# Gagabiro_POC_PSU_main.net
KiCad netlist of a schematic drawn in Altium Designer
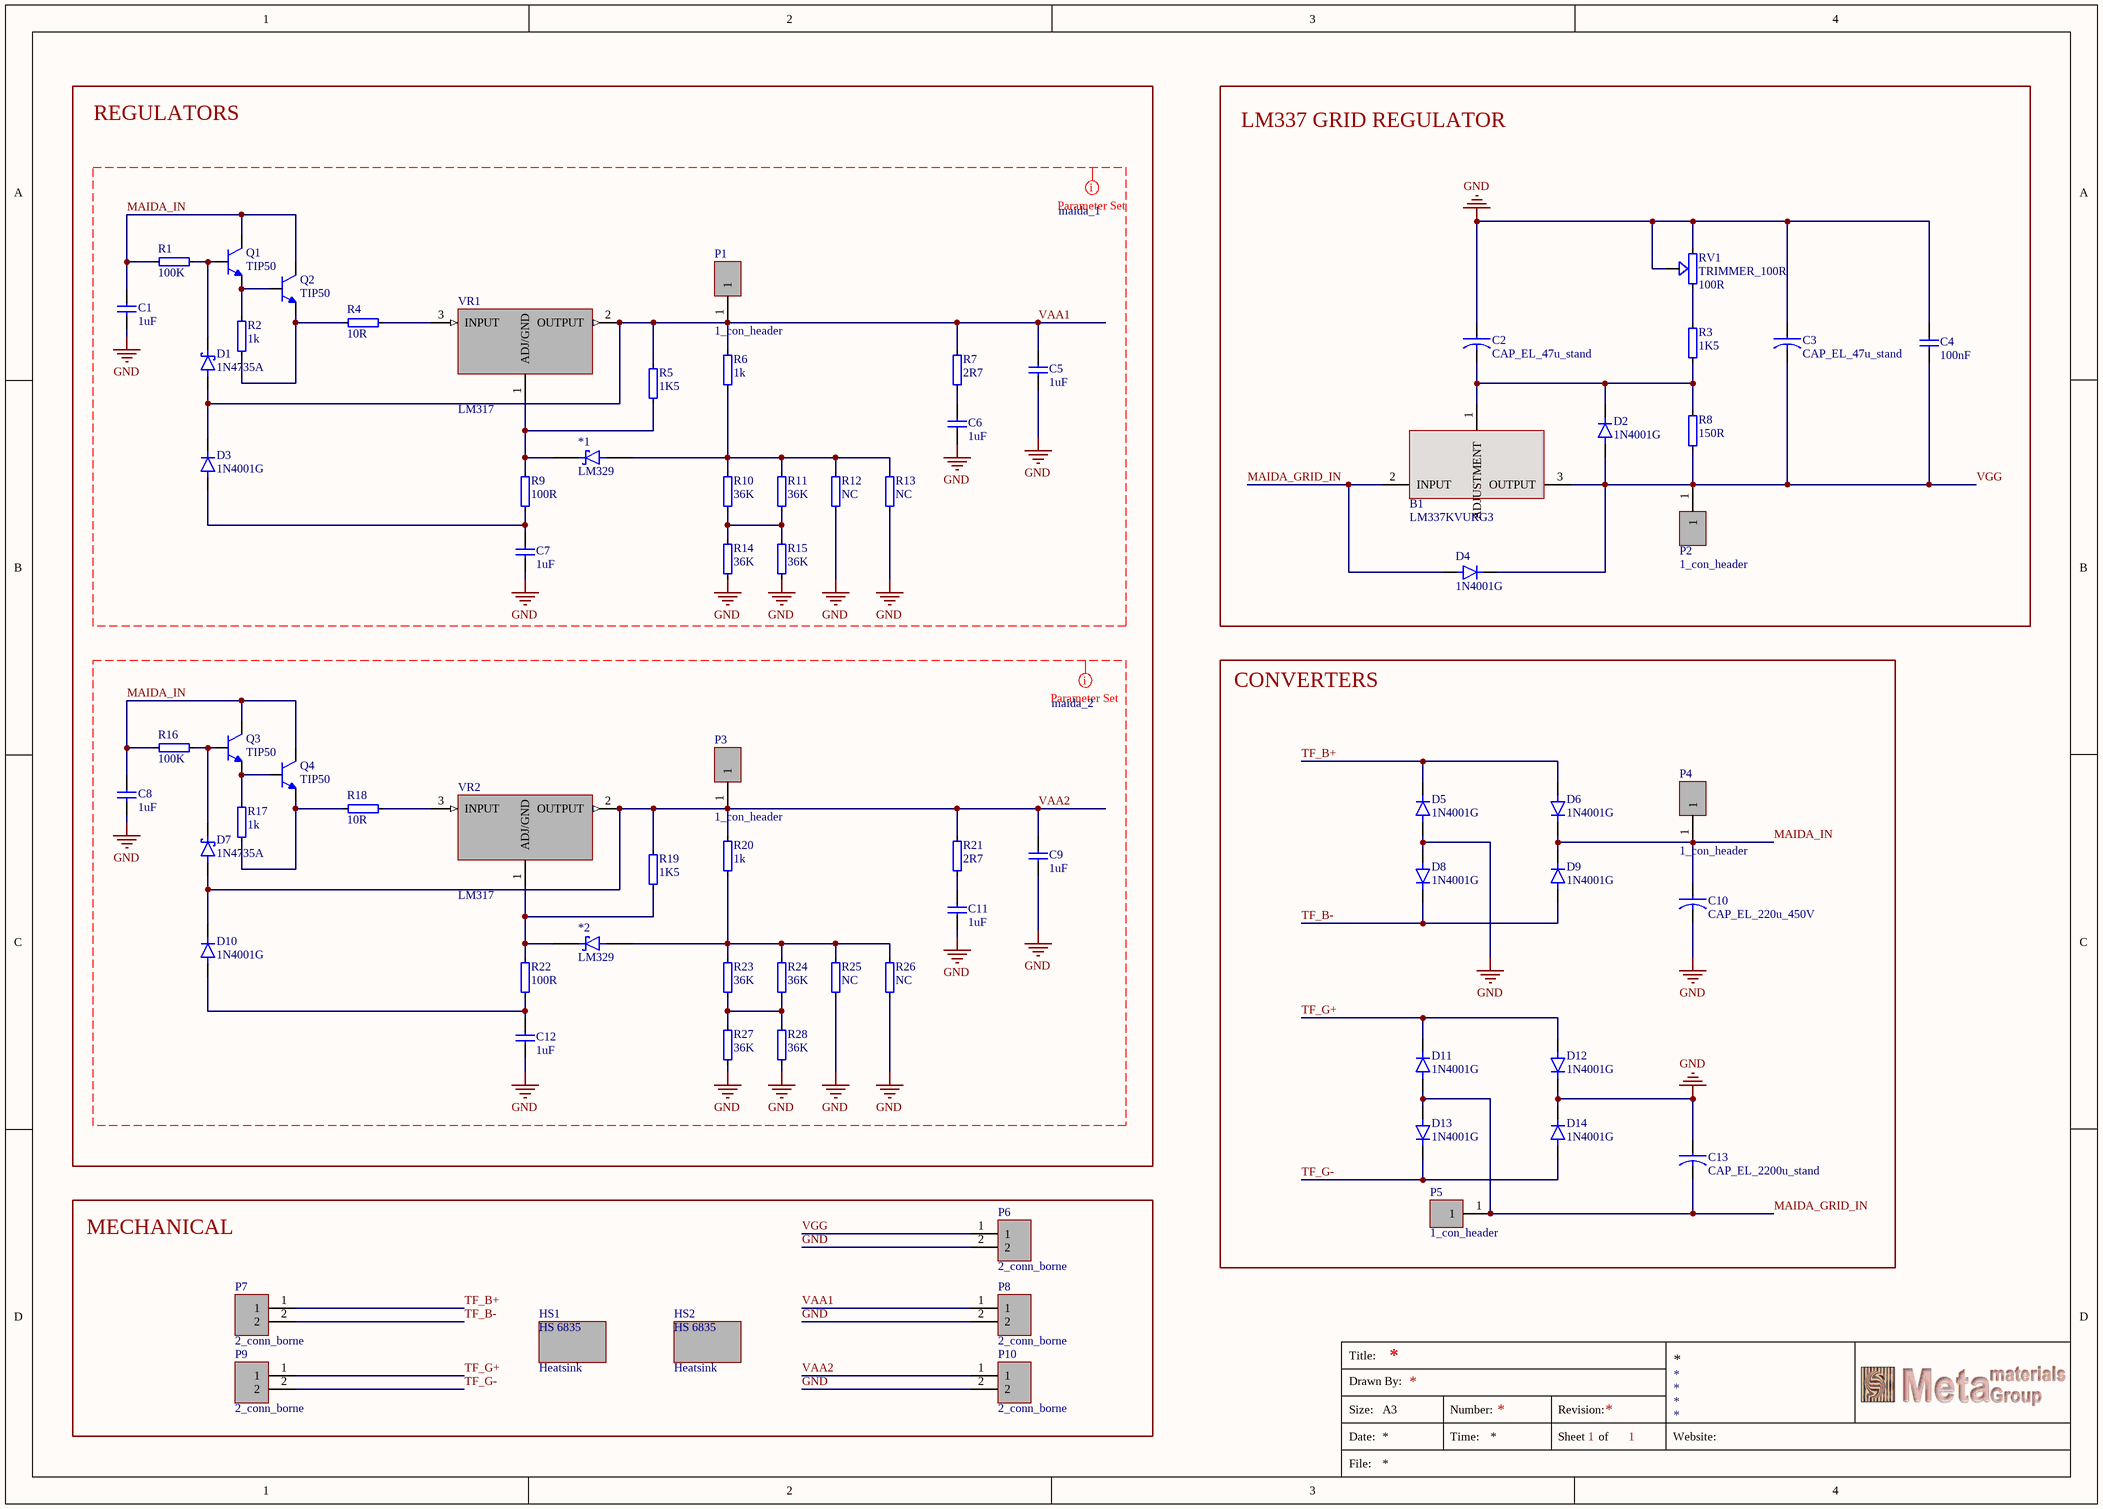
[diagram p0: Gagabiro_POC_PSU_main.SchDoc]

(export (version "E")
  (design (tool "Eeschema 10.0.6"))
  (components
    (comp (ref "*1")
      (value "LM329")
      (footprint "Gagabiro:TO92127P495H495-3")
      (libsource (lib "Gagabiro") (part "LM329"))
    )
    (comp (ref "*2")
      (value "LM329")
      (footprint "Gagabiro:TO92127P495H495-3")
      (libsource (lib "Gagabiro") (part "LM329"))
    )
    (comp (ref "B1")
      (value "LM337KVURG3")
      (footprint "lm317")
      (description "3 Pin 1.5A Adjustable Negative Voltage Regulator")
      (fields (field (name "MOUSER PART NUMBER") "595-LM337KVURG3"))
      (libsource (lib "Gagabiro") (part "LM337"))
    )
    (comp (ref "C1")
      (value "1uF")
      (footprint "Gagabiro:CAP_panassonic_1u_450V")
      (description "Capacitor, Silver Mica")
      (fields (field (name "PART NUMBER") "CMICA_47PF"))
      (libsource (lib "Gagabiro") (part "CAP_POLY_1u"))
    )
    (comp (ref "C2")
      (value "CAP_EL_47u_stand")
      (footprint "Gagabiro:CAPPRD500W50D630H1120_stand")
      (description "220F 16V Aluminum Electrolytic Capacitors Radial, Can 1000 Hrs @ 105C")
      (fields (field (name "MP") "EEU-HD1C221B") (field (name "MF") "Panasonic"))
      (libsource (lib "Gagabiro") (part "CAP_EL_47u_stand"))
    )
    (comp (ref "C3")
      (value "CAP_EL_47u_stand")
      (footprint "Gagabiro:CAPPRD500W50D630H1120_stand")
      (description "220F 16V Aluminum Electrolytic Capacitors Radial, Can 1000 Hrs @ 105C")
      (fields (field (name "MP") "EEU-HD1C221B") (field (name "MF") "Panasonic"))
      (libsource (lib "Gagabiro") (part "CAP_EL_47u_stand"))
    )
    (comp (ref "C4")
      (value "100nF")
      (footprint "Gagabiro:CAP_panassonic_100n_450V")
      (description "Capacitor, Silver Mica")
      (fields (field (name "PART NUMBER") "CMICA_47PF"))
      (libsource (lib "Gagabiro") (part "CAP_POLY_100n"))
    )
    (comp (ref "C5")
      (value "1uF")
      (footprint "Gagabiro:CAP_panassonic_1u_450V")
      (description "Capacitor, Silver Mica")
      (fields (field (name "PART NUMBER") "CMICA_47PF"))
      (libsource (lib "Gagabiro") (part "CAP_POLY_1u"))
    )
    (comp (ref "C6")
      (value "1uF")
      (footprint "Gagabiro:CAP_panassonic_1u_450V")
      (description "Capacitor, Silver Mica")
      (fields (field (name "PART NUMBER") "CMICA_47PF"))
      (libsource (lib "Gagabiro") (part "CAP_POLY_1u"))
    )
    (comp (ref "C7")
      (value "1uF")
      (footprint "Gagabiro:CAP_panassonic_1u_450V")
      (description "Capacitor, Silver Mica")
      (fields (field (name "PART NUMBER") "CMICA_47PF"))
      (libsource (lib "Gagabiro") (part "CAP_POLY_1u"))
    )
    (comp (ref "C8")
      (value "1uF")
      (footprint "Gagabiro:CAP_panassonic_1u_450V")
      (description "Capacitor, Silver Mica")
      (fields (field (name "PART NUMBER") "CMICA_47PF"))
      (libsource (lib "Gagabiro") (part "CAP_POLY_1u"))
    )
    (comp (ref "C9")
      (value "1uF")
      (footprint "Gagabiro:CAP_panassonic_1u_450V")
      (description "Capacitor, Silver Mica")
      (fields (field (name "PART NUMBER") "CMICA_47PF"))
      (libsource (lib "Gagabiro") (part "CAP_POLY_1u"))
    )
    (comp (ref "C10")
      (value "CAP_EL_220u_450V")
      (footprint "Gagabiro:CAPPRD500W50D630H1120_stand_25x50")
      (description "220F 16V Aluminum Electrolytic Capacitors Radial, Can 1000 Hrs @ 105C")
      (fields (field (name "MP") "EEU-HD1C221B") (field (name "MF") "Panasonic"))
      (libsource (lib "Persephone") (part "CAP_EL_220u_450V"))
    )
    (comp (ref "C11")
      (value "1uF")
      (footprint "Gagabiro:CAP_panassonic_1u_450V")
      (description "Capacitor, Silver Mica")
      (fields (field (name "PART NUMBER") "CMICA_47PF"))
      (libsource (lib "Gagabiro") (part "CAP_POLY_1u"))
    )
    (comp (ref "C12")
      (value "1uF")
      (footprint "Gagabiro:CAP_panassonic_1u_450V")
      (description "Capacitor, Silver Mica")
      (fields (field (name "PART NUMBER") "CMICA_47PF"))
      (libsource (lib "Gagabiro") (part "CAP_POLY_1u"))
    )
    (comp (ref "C13")
      (value "CAP_EL_2200u_stand")
      (footprint "Gagabiro:CAPPRD500W50D630H1120_stand_22x40")
      (description "220F 16V Aluminum Electrolytic Capacitors Radial, Can 1000 Hrs @ 105C")
      (fields (field (name "MP") "EEU-HD1C221B") (field (name "MF") "Panasonic"))
      (libsource (lib "Gagabiro") (part "CAP_EL_2200u_stand"))
    )
    (comp (ref "D1")
      (value "1N4735A")
      (footprint "Gagabiro:DIOAD1036W78L463D272")
      (description "Zener Diode 6.2V 1W Â±5% Through Hole DO-204AL (DO-41)")
      (fields (field (name "MF") "ON Semiconductor"))
      (libsource (lib "Gagabiro") (part "1N4735A"))
    )
    (comp (ref "D2")
      (value "1N4001G")
      (footprint "Gagabiro:DIOAD1036W78L470D235")
      (description "1A, 50V, Standard Recovery Rectifier")
      (fields (field (name "MF") "Taiwan Semiconductor"))
      (libsource (lib "Gagabiro") (part "1N4001G"))
    )
    (comp (ref "D3")
      (value "1N4001G")
      (footprint "Gagabiro:DIOAD1036W78L470D235")
      (description "1A, 50V, Standard Recovery Rectifier")
      (fields (field (name "MF") "Taiwan Semiconductor"))
      (libsource (lib "Gagabiro") (part "1N4001G"))
    )
    (comp (ref "D4")
      (value "1N4001G")
      (footprint "Gagabiro:DIOAD1036W78L470D235")
      (description "1A, 50V, Standard Recovery Rectifier")
      (fields (field (name "MF") "Taiwan Semiconductor"))
      (libsource (lib "Gagabiro") (part "1N4001G"))
    )
    (comp (ref "D5")
      (value "1N4001G")
      (footprint "Gagabiro:DIOAD1036W78L470D235")
      (description "1A, 50V, Standard Recovery Rectifier")
      (fields (field (name "MF") "Taiwan Semiconductor"))
      (libsource (lib "Gagabiro") (part "1N4001G"))
    )
    (comp (ref "D6")
      (value "1N4001G")
      (footprint "Gagabiro:DIOAD1036W78L470D235")
      (description "1A, 50V, Standard Recovery Rectifier")
      (fields (field (name "MF") "Taiwan Semiconductor"))
      (libsource (lib "Gagabiro") (part "1N4001G"))
    )
    (comp (ref "D7")
      (value "1N4735A")
      (footprint "Gagabiro:DIOAD1036W78L463D272")
      (description "Zener Diode 6.2V 1W Â±5% Through Hole DO-204AL (DO-41)")
      (fields (field (name "MF") "ON Semiconductor"))
      (libsource (lib "Gagabiro") (part "1N4735A"))
    )
    (comp (ref "D8")
      (value "1N4001G")
      (footprint "Gagabiro:DIOAD1036W78L470D235")
      (description "1A, 50V, Standard Recovery Rectifier")
      (fields (field (name "MF") "Taiwan Semiconductor"))
      (libsource (lib "Gagabiro") (part "1N4001G"))
    )
    (comp (ref "D9")
      (value "1N4001G")
      (footprint "Gagabiro:DIOAD1036W78L470D235")
      (description "1A, 50V, Standard Recovery Rectifier")
      (fields (field (name "MF") "Taiwan Semiconductor"))
      (libsource (lib "Gagabiro") (part "1N4001G"))
    )
    (comp (ref "D10")
      (value "1N4001G")
      (footprint "Gagabiro:DIOAD1036W78L470D235")
      (description "1A, 50V, Standard Recovery Rectifier")
      (fields (field (name "MF") "Taiwan Semiconductor"))
      (libsource (lib "Gagabiro") (part "1N4001G"))
    )
    (comp (ref "D11")
      (value "1N4001G")
      (footprint "Gagabiro:DIOAD1036W78L470D235")
      (description "1A, 50V, Standard Recovery Rectifier")
      (fields (field (name "MF") "Taiwan Semiconductor"))
      (libsource (lib "Gagabiro") (part "1N4001G"))
    )
    (comp (ref "D12")
      (value "1N4001G")
      (footprint "Gagabiro:DIOAD1036W78L470D235")
      (description "1A, 50V, Standard Recovery Rectifier")
      (fields (field (name "MF") "Taiwan Semiconductor"))
      (libsource (lib "Gagabiro") (part "1N4001G"))
    )
    (comp (ref "D13")
      (value "1N4001G")
      (footprint "Gagabiro:DIOAD1036W78L470D235")
      (description "1A, 50V, Standard Recovery Rectifier")
      (fields (field (name "MF") "Taiwan Semiconductor"))
      (libsource (lib "Gagabiro") (part "1N4001G"))
    )
    (comp (ref "D14")
      (value "1N4001G")
      (footprint "Gagabiro:DIOAD1036W78L470D235")
      (description "1A, 50V, Standard Recovery Rectifier")
      (fields (field (name "MF") "Taiwan Semiconductor"))
      (libsource (lib "Gagabiro") (part "1N4001G"))
    )
    (comp (ref "HS1")
      (value "Heatsink")
      (footprint "Gagabiro:heatsink_HS_6835")
      (libsource (lib "Gagabiro") (part "HS 6835"))
    )
    (comp (ref "HS2")
      (value "Heatsink")
      (footprint "Gagabiro:heatsink_HS_6835")
      (libsource (lib "Gagabiro") (part "HS 6835"))
    )
    (comp (ref "P1")
      (value "1_con_header")
      (footprint "Gagabiro:SAMTEC_MTMM-101-X-X-S-X")
      (description "Connector Header Surface Mount, Right Angle 2 position 0.079 (2.00mm)")
      (fields (field (name "MP") "S2B-PH-SM4-TB") (field (name "MF") "JST Sales"))
      (libsource (lib "Gagabiro") (part "1_con_header"))
    )
    (comp (ref "P2")
      (value "1_con_header")
      (footprint "Gagabiro:SAMTEC_MTMM-101-X-X-S-X")
      (description "Connector Header Surface Mount, Right Angle 2 position 0.079 (2.00mm)")
      (fields (field (name "MP") "S2B-PH-SM4-TB") (field (name "MF") "JST Sales"))
      (libsource (lib "") (part "1_con_header_1"))
    )
    (comp (ref "P3")
      (value "1_con_header")
      (footprint "Gagabiro:SAMTEC_MTMM-101-X-X-S-X")
      (description "Connector Header Surface Mount, Right Angle 2 position 0.079 (2.00mm)")
      (fields (field (name "MP") "S2B-PH-SM4-TB") (field (name "MF") "JST Sales"))
      (libsource (lib "Gagabiro") (part "1_con_header"))
    )
    (comp (ref "P4")
      (value "1_con_header")
      (footprint "Gagabiro:SAMTEC_MTMM-101-X-X-S-X")
      (description "Connector Header Surface Mount, Right Angle 2 position 0.079 (2.00mm)")
      (fields (field (name "MP") "S2B-PH-SM4-TB") (field (name "MF") "JST Sales"))
      (libsource (lib "Gagabiro") (part "1_con_header"))
    )
    (comp (ref "P5")
      (value "1_con_header")
      (footprint "Gagabiro:SAMTEC_MTMM-101-X-X-S-X")
      (description "Connector Header Surface Mount, Right Angle 2 position 0.079 (2.00mm)")
      (fields (field (name "MP") "S2B-PH-SM4-TB") (field (name "MF") "JST Sales"))
      (libsource (lib "") (part "1_con_header_2"))
    )
    (comp (ref "P6")
      (value "2_conn_borne")
      (footprint "691101710002")
      (description "Connector Header Surface Mount, Right Angle 2 position 0.079 (2.00mm)")
      (fields (field (name "MP") "S2B-PH-SM4-TB") (field (name "MF") "JST Sales"))
      (libsource (lib "") (part "2_conn_borne_1"))
    )
    (comp (ref "P7")
      (value "2_conn_borne")
      (footprint "691101710002")
      (description "Connector Header Surface Mount, Right Angle 2 position 0.079 (2.00mm)")
      (fields (field (name "MP") "S2B-PH-SM4-TB") (field (name "MF") "JST Sales"))
      (libsource (lib "Gagabiro") (part "2_conn_borne"))
    )
    (comp (ref "P8")
      (value "2_conn_borne")
      (footprint "691101710002")
      (description "Connector Header Surface Mount, Right Angle 2 position 0.079 (2.00mm)")
      (fields (field (name "MP") "S2B-PH-SM4-TB") (field (name "MF") "JST Sales"))
      (libsource (lib "") (part "2_conn_borne_1"))
    )
    (comp (ref "P9")
      (value "2_conn_borne")
      (footprint "691101710002")
      (description "Connector Header Surface Mount, Right Angle 2 position 0.079 (2.00mm)")
      (fields (field (name "MP") "S2B-PH-SM4-TB") (field (name "MF") "JST Sales"))
      (libsource (lib "Gagabiro") (part "2_conn_borne"))
    )
    (comp (ref "P10")
      (value "2_conn_borne")
      (footprint "691101710002")
      (description "Connector Header Surface Mount, Right Angle 2 position 0.079 (2.00mm)")
      (fields (field (name "MP") "S2B-PH-SM4-TB") (field (name "MF") "JST Sales"))
      (libsource (lib "") (part "2_conn_borne_1"))
    )
    (comp (ref "Q1")
      (value "TIP50")
      (footprint "Gagabiro:TO254P1009X445X1985-3")
      (description "Bipolar (BJT) Transistor NPN 400 V 1 A 10MHz 2 W Through Hole TO-220-3")
      (fields (field (name "MF") "ON Semiconductor"))
      (libsource (lib "Gagabiro") (part "TIP50"))
    )
    (comp (ref "Q2")
      (value "TIP50")
      (footprint "Gagabiro:TO254P1009X445X1985-3")
      (description "Bipolar (BJT) Transistor NPN 400 V 1 A 10MHz 2 W Through Hole TO-220-3")
      (fields (field (name "MF") "ON Semiconductor"))
      (libsource (lib "Gagabiro") (part "TIP50"))
    )
    (comp (ref "Q3")
      (value "TIP50")
      (footprint "Gagabiro:TO254P1009X445X1985-3")
      (description "Bipolar (BJT) Transistor NPN 400 V 1 A 10MHz 2 W Through Hole TO-220-3")
      (fields (field (name "MF") "ON Semiconductor"))
      (libsource (lib "Gagabiro") (part "TIP50"))
    )
    (comp (ref "Q4")
      (value "TIP50")
      (footprint "Gagabiro:TO254P1009X445X1985-3")
      (description "Bipolar (BJT) Transistor NPN 400 V 1 A 10MHz 2 W Through Hole TO-220-3")
      (fields (field (name "MF") "ON Semiconductor"))
      (libsource (lib "Gagabiro") (part "TIP50"))
    )
    (comp (ref "R1")
      (value "100K")
      (footprint "Gagabiro:RES_2W_vertical")
      (description "Resistor, 2W")
      (fields (field (name "PART NUMBER") "R2W") (field (name "AUTHOR") "colombari"))
      (libsource (lib "Gagabiro") (part "R_2W_vertical_100K"))
    )
    (comp (ref "R2")
      (value "1k")
      (footprint "Gagabiro:RES_2W_vertical")
      (description "Resistor, 2W")
      (fields (field (name "PART NUMBER") "R2W") (field (name "AUTHOR") "colombari"))
      (libsource (lib "Gagabiro") (part "R_2W_vertical_1k"))
    )
    (comp (ref "R3")
      (value "1K5")
      (footprint "Gagabiro:RES_2W_vertical")
      (description "Resistor, 2W")
      (fields (field (name "PART NUMBER") "R2W") (field (name "AUTHOR") "colombari"))
      (libsource (lib "Gagabiro") (part "R_2W_vertical_1K5"))
    )
    (comp (ref "R4")
      (value "10R")
      (footprint "Gagabiro:RES_2W_vertical")
      (description "Resistor, 2W")
      (fields (field (name "PART NUMBER") "R2W") (field (name "AUTHOR") "colombari"))
      (libsource (lib "Gagabiro") (part "R_2W_vertical_10R"))
    )
    (comp (ref "R5")
      (value "1K5")
      (footprint "Gagabiro:RES_2W_vertical")
      (description "Resistor, 2W")
      (fields (field (name "PART NUMBER") "R2W") (field (name "AUTHOR") "colombari"))
      (libsource (lib "Gagabiro") (part "R_2W_vertical_1K5"))
    )
    (comp (ref "R6")
      (value "1k")
      (footprint "Gagabiro:RES_2W_vertical")
      (description "Resistor, 2W")
      (fields (field (name "PART NUMBER") "R2W") (field (name "AUTHOR") "colombari"))
      (libsource (lib "Gagabiro") (part "R_2W_vertical_1k"))
    )
    (comp (ref "R7")
      (value "2R7")
      (footprint "Gagabiro:RES_2W_vertical")
      (description "Resistor, 2W")
      (fields (field (name "PART NUMBER") "R2W") (field (name "AUTHOR") "colombari"))
      (libsource (lib "Gagabiro") (part "R_2W_vertical_2R7"))
    )
    (comp (ref "R8")
      (value "150R")
      (footprint "Gagabiro:RES_2W_vertical")
      (description "Resistor, 2W")
      (fields (field (name "PART NUMBER") "R2W") (field (name "AUTHOR") "colombari"))
      (libsource (lib "Gagabiro") (part "R_2W_vertical_150R"))
    )
    (comp (ref "R9")
      (value "100R")
      (footprint "Gagabiro:RES_2W_vertical")
      (description "Resistor, 2W")
      (fields (field (name "PART NUMBER") "R2W") (field (name "AUTHOR") "colombari"))
      (libsource (lib "Gagabiro") (part "R_2W_vertical_100R"))
    )
    (comp (ref "R10")
      (value "36K")
      (footprint "Gagabiro:RES_2W_vertical")
      (description "Resistor, 2W")
      (fields (field (name "PART NUMBER") "R2W") (field (name "AUTHOR") "colombari"))
      (libsource (lib "Gagabiro") (part "R_2W_vertical_36K"))
    )
    (comp (ref "R11")
      (value "36K")
      (footprint "Gagabiro:RES_2W_vertical")
      (description "Resistor, 2W")
      (fields (field (name "PART NUMBER") "R2W") (field (name "AUTHOR") "colombari"))
      (libsource (lib "Gagabiro") (part "R_2W_vertical_36K"))
    )
    (comp (ref "R12")
      (value "NC")
      (footprint "Gagabiro:RES_2W_vertical")
      (description "Resistor, 2W")
      (fields (field (name "PART NUMBER") "R2W") (field (name "AUTHOR") "colombari"))
      (libsource (lib "Gagabiro") (part "R_2W_vertical_NC"))
    )
    (comp (ref "R13")
      (value "NC")
      (footprint "Gagabiro:RES_2W_vertical")
      (description "Resistor, 2W")
      (fields (field (name "PART NUMBER") "R2W") (field (name "AUTHOR") "colombari"))
      (libsource (lib "Gagabiro") (part "R_2W_vertical_NC"))
    )
    (comp (ref "R14")
      (value "36K")
      (footprint "Gagabiro:RES_2W_vertical")
      (description "Resistor, 2W")
      (fields (field (name "PART NUMBER") "R2W") (field (name "AUTHOR") "colombari"))
      (libsource (lib "Gagabiro") (part "R_2W_vertical_36K"))
    )
    (comp (ref "R15")
      (value "36K")
      (footprint "Gagabiro:RES_2W_vertical")
      (description "Resistor, 2W")
      (fields (field (name "PART NUMBER") "R2W") (field (name "AUTHOR") "colombari"))
      (libsource (lib "Gagabiro") (part "R_2W_vertical_36K"))
    )
    (comp (ref "R16")
      (value "100K")
      (footprint "Gagabiro:RES_2W_vertical")
      (description "Resistor, 2W")
      (fields (field (name "PART NUMBER") "R2W") (field (name "AUTHOR") "colombari"))
      (libsource (lib "Gagabiro") (part "R_2W_vertical_100K"))
    )
    (comp (ref "R17")
      (value "1k")
      (footprint "Gagabiro:RES_2W_vertical")
      (description "Resistor, 2W")
      (fields (field (name "PART NUMBER") "R2W") (field (name "AUTHOR") "colombari"))
      (libsource (lib "Gagabiro") (part "R_2W_vertical_1k"))
    )
    (comp (ref "R18")
      (value "10R")
      (footprint "Gagabiro:RES_2W_vertical")
      (description "Resistor, 2W")
      (fields (field (name "PART NUMBER") "R2W") (field (name "AUTHOR") "colombari"))
      (libsource (lib "Gagabiro") (part "R_2W_vertical_10R"))
    )
    (comp (ref "R19")
      (value "1K5")
      (footprint "Gagabiro:RES_2W_vertical")
      (description "Resistor, 2W")
      (fields (field (name "PART NUMBER") "R2W") (field (name "AUTHOR") "colombari"))
      (libsource (lib "Gagabiro") (part "R_2W_vertical_1K5"))
    )
    (comp (ref "R20")
      (value "1k")
      (footprint "Gagabiro:RES_2W_vertical")
      (description "Resistor, 2W")
      (fields (field (name "PART NUMBER") "R2W") (field (name "AUTHOR") "colombari"))
      (libsource (lib "Gagabiro") (part "R_2W_vertical_1k"))
    )
    (comp (ref "R21")
      (value "2R7")
      (footprint "Gagabiro:RES_2W_vertical")
      (description "Resistor, 2W")
      (fields (field (name "PART NUMBER") "R2W") (field (name "AUTHOR") "colombari"))
      (libsource (lib "Gagabiro") (part "R_2W_vertical_2R7"))
    )
    (comp (ref "R22")
      (value "100R")
      (footprint "Gagabiro:RES_2W_vertical")
      (description "Resistor, 2W")
      (fields (field (name "PART NUMBER") "R2W") (field (name "AUTHOR") "colombari"))
      (libsource (lib "Gagabiro") (part "R_2W_vertical_100R"))
    )
    (comp (ref "R23")
      (value "36K")
      (footprint "Gagabiro:RES_2W_vertical")
      (description "Resistor, 2W")
      (fields (field (name "PART NUMBER") "R2W") (field (name "AUTHOR") "colombari"))
      (libsource (lib "Gagabiro") (part "R_2W_vertical_36K"))
    )
    (comp (ref "R24")
      (value "36K")
      (footprint "Gagabiro:RES_2W_vertical")
      (description "Resistor, 2W")
      (fields (field (name "PART NUMBER") "R2W") (field (name "AUTHOR") "colombari"))
      (libsource (lib "Gagabiro") (part "R_2W_vertical_36K"))
    )
    (comp (ref "R25")
      (value "NC")
      (footprint "Gagabiro:RES_2W_vertical")
      (description "Resistor, 2W")
      (fields (field (name "PART NUMBER") "R2W") (field (name "AUTHOR") "colombari"))
      (libsource (lib "Gagabiro") (part "R_2W_vertical_NC"))
    )
    (comp (ref "R26")
      (value "NC")
      (footprint "Gagabiro:RES_2W_vertical")
      (description "Resistor, 2W")
      (fields (field (name "PART NUMBER") "R2W") (field (name "AUTHOR") "colombari"))
      (libsource (lib "Gagabiro") (part "R_2W_vertical_NC"))
    )
    (comp (ref "R27")
      (value "36K")
      (footprint "Gagabiro:RES_2W_vertical")
      (description "Resistor, 2W")
      (fields (field (name "PART NUMBER") "R2W") (field (name "AUTHOR") "colombari"))
      (libsource (lib "Gagabiro") (part "R_2W_vertical_36K"))
    )
    (comp (ref "R28")
      (value "36K")
      (footprint "Gagabiro:RES_2W_vertical")
      (description "Resistor, 2W")
      (fields (field (name "PART NUMBER") "R2W") (field (name "AUTHOR") "colombari"))
      (libsource (lib "Gagabiro") (part "R_2W_vertical_36K"))
    )
    (comp (ref "RV1")
      (value "TRIMMER_100R")
      (footprint "Gagabiro:TRIM_PV36W204C01B00 - duplicate")
      (description "TRIMMER")
      (fields
        (field (name "MF") "Bourns Electronics")
        (field (name "MP") "PV36W204C01B00.")
        (field (name "ALTIUM_VALUE") "100R")
      )
      (libsource (lib "Gagabiro") (part "TRIMMER_100R"))
    )
    (comp (ref "VR1")
      (value "LM317")
      (footprint "Gagabiro:TO254P1009X445X1985-3")
      (fields (field (name "MP") "LM317AMDT/NOPB"))
      (libsource (lib "Gagabiro") (part "LM317"))
    )
    (comp (ref "VR2")
      (value "LM317")
      (footprint "Gagabiro:TO254P1009X445X1985-3")
      (fields (field (name "MP") "LM317AMDT/NOPB"))
      (libsource (lib "Gagabiro") (part "LM317"))
    )
  )
  (nets
    (net (code "1") (name "/MAIDA_GRID_IN") (class "Default")
      (node (ref "B1") (pin "2") (pinfunction "INPUT_2") (pintype "passive"))
      (node (ref "C13") (pin "N") (pinfunction "N_N") (pintype "passive"))
      (node (ref "D11") (pin "A") (pinfunction "A_A") (pintype "passive"))
      (node (ref "D13") (pin "A") (pinfunction "A_A") (pintype "passive"))
      (node (ref "D4") (pin "A") (pinfunction "A_A") (pintype "passive"))
      (node (ref "P5") (pin "1") (pinfunction "1_1") (pintype "passive"))
    )
    (net (code "2") (name "/MAIDA_IN") (class "Default")
      (node (ref "C1") (pin "2") (pinfunction "2_2") (pintype "passive"))
      (node (ref "C10") (pin "P") (pinfunction "P_P") (pintype "passive"))
      (node (ref "C8") (pin "2") (pinfunction "2_2") (pintype "passive"))
      (node (ref "D6") (pin "C") (pinfunction "K_C") (pintype "passive"))
      (node (ref "D9") (pin "C") (pinfunction "K_C") (pintype "passive"))
      (node (ref "P4") (pin "1") (pinfunction "1_1") (pintype "passive"))
      (node (ref "Q1") (pin "2") (pinfunction "C_2") (pintype "passive"))
      (node (ref "Q2") (pin "2") (pinfunction "C_2") (pintype "passive"))
      (node (ref "Q3") (pin "2") (pinfunction "C_2") (pintype "passive"))
      (node (ref "Q4") (pin "2") (pinfunction "C_2") (pintype "passive"))
      (node (ref "R1") (pin "1") (pinfunction "1_1") (pintype "passive"))
      (node (ref "R16") (pin "1") (pinfunction "1_1") (pintype "passive"))
    )
    (net (code "3") (name "/TF_B+") (class "Default")
      (node (ref "D5") (pin "C") (pinfunction "K_C") (pintype "passive"))
      (node (ref "D6") (pin "A") (pinfunction "A_A") (pintype "passive"))
      (node (ref "P7") (pin "1") (pinfunction "1_1") (pintype "passive"))
    )
    (net (code "4") (name "/TF_B-") (class "Default")
      (node (ref "D8") (pin "C") (pinfunction "K_C") (pintype "passive"))
      (node (ref "D9") (pin "A") (pinfunction "A_A") (pintype "passive"))
      (node (ref "P7") (pin "2") (pinfunction "2_2") (pintype "passive"))
    )
    (net (code "5") (name "/TF_G+") (class "Default")
      (node (ref "D11") (pin "C") (pinfunction "K_C") (pintype "passive"))
      (node (ref "D12") (pin "A") (pinfunction "A_A") (pintype "passive"))
      (node (ref "P9") (pin "1") (pinfunction "1_1") (pintype "passive"))
    )
    (net (code "6") (name "/TF_G-") (class "Default")
      (node (ref "D13") (pin "C") (pinfunction "K_C") (pintype "passive"))
      (node (ref "D14") (pin "A") (pinfunction "A_A") (pintype "passive"))
      (node (ref "P9") (pin "2") (pinfunction "2_2") (pintype "passive"))
    )
    (net (code "7") (name "/VAA1") (class "Default")
      (node (ref "C5") (pin "2") (pinfunction "2_2") (pintype "passive"))
      (node (ref "D1") (pin "2") (pinfunction "A_2") (pintype "passive"))
      (node (ref "D3") (pin "C") (pinfunction "K_C") (pintype "passive"))
      (node (ref "P1") (pin "1") (pinfunction "1_1") (pintype "passive"))
      (node (ref "P8") (pin "1") (pinfunction "1_1") (pintype "passive"))
      (node (ref "R5") (pin "1") (pinfunction "1_1") (pintype "passive"))
      (node (ref "R6") (pin "2") (pinfunction "2_2") (pintype "passive"))
      (node (ref "R7") (pin "2") (pinfunction "2_2") (pintype "passive"))
      (node (ref "VR1") (pin "2") (pinfunction "OUTPUT_2") (pintype "output"))
    )
    (net (code "8") (name "/VAA2") (class "Default")
      (node (ref "C9") (pin "2") (pinfunction "2_2") (pintype "passive"))
      (node (ref "D10") (pin "C") (pinfunction "K_C") (pintype "passive"))
      (node (ref "D7") (pin "2") (pinfunction "A_2") (pintype "passive"))
      (node (ref "P10") (pin "1") (pinfunction "1_1") (pintype "passive"))
      (node (ref "P3") (pin "1") (pinfunction "1_1") (pintype "passive"))
      (node (ref "R19") (pin "1") (pinfunction "1_1") (pintype "passive"))
      (node (ref "R20") (pin "2") (pinfunction "2_2") (pintype "passive"))
      (node (ref "R21") (pin "2") (pinfunction "2_2") (pintype "passive"))
      (node (ref "VR2") (pin "2") (pinfunction "OUTPUT_2") (pintype "output"))
    )
    (net (code "9") (name "/VGG") (class "Default")
      (node (ref "B1") (pin "3") (pinfunction "OUTPUT_3") (pintype "passive"))
      (node (ref "C3") (pin "N") (pinfunction "N_N") (pintype "passive"))
      (node (ref "C4") (pin "1") (pinfunction "1_1") (pintype "passive"))
      (node (ref "D2") (pin "A") (pinfunction "A_A") (pintype "passive"))
      (node (ref "D4") (pin "C") (pinfunction "K_C") (pintype "passive"))
      (node (ref "P2") (pin "1") (pinfunction "1_1") (pintype "passive"))
      (node (ref "P6") (pin "1") (pinfunction "1_1") (pintype "passive"))
      (node (ref "R8") (pin "1") (pinfunction "1_1") (pintype "passive"))
    )
    (net (code "10") (name "GND") (class "Default")
      (node (ref "C1") (pin "1") (pinfunction "1_1") (pintype "passive"))
      (node (ref "C10") (pin "N") (pinfunction "N_N") (pintype "passive"))
      (node (ref "C11") (pin "1") (pinfunction "1_1") (pintype "passive"))
      (node (ref "C12") (pin "1") (pinfunction "1_1") (pintype "passive"))
      (node (ref "C13") (pin "P") (pinfunction "P_P") (pintype "passive"))
      (node (ref "C2") (pin "P") (pinfunction "P_P") (pintype "passive"))
      (node (ref "C3") (pin "P") (pinfunction "P_P") (pintype "passive"))
      (node (ref "C4") (pin "2") (pinfunction "2_2") (pintype "passive"))
      (node (ref "C5") (pin "1") (pinfunction "1_1") (pintype "passive"))
      (node (ref "C6") (pin "1") (pinfunction "1_1") (pintype "passive"))
      (node (ref "C7") (pin "1") (pinfunction "1_1") (pintype "passive"))
      (node (ref "C8") (pin "1") (pinfunction "1_1") (pintype "passive"))
      (node (ref "C9") (pin "1") (pinfunction "1_1") (pintype "passive"))
      (node (ref "D12") (pin "C") (pinfunction "K_C") (pintype "passive"))
      (node (ref "D14") (pin "C") (pinfunction "K_C") (pintype "passive"))
      (node (ref "D5") (pin "A") (pinfunction "A_A") (pintype "passive"))
      (node (ref "D8") (pin "A") (pinfunction "A_A") (pintype "passive"))
      (node (ref "P10") (pin "2") (pinfunction "2_2") (pintype "passive"))
      (node (ref "P6") (pin "2") (pinfunction "2_2") (pintype "passive"))
      (node (ref "P8") (pin "2") (pinfunction "2_2") (pintype "passive"))
      (node (ref "R12") (pin "1") (pinfunction "1_1") (pintype "passive"))
      (node (ref "R13") (pin "1") (pinfunction "1_1") (pintype "passive"))
      (node (ref "R14") (pin "1") (pinfunction "1_1") (pintype "passive"))
      (node (ref "R15") (pin "1") (pinfunction "1_1") (pintype "passive"))
      (node (ref "R25") (pin "1") (pinfunction "1_1") (pintype "passive"))
      (node (ref "R26") (pin "1") (pinfunction "1_1") (pintype "passive"))
      (node (ref "R27") (pin "1") (pinfunction "1_1") (pintype "passive"))
      (node (ref "R28") (pin "1") (pinfunction "1_1") (pintype "passive"))
      (node (ref "RV1") (pin "2") (pinfunction "2_2") (pintype "passive"))
      (node (ref "RV1") (pin "3") (pinfunction "3_3") (pintype "passive"))
    )
    (net (code "11") (name "Net-(*1-Pad3)") (class "Default")
      (node (ref "*1") (pin "3") (pinfunction "3_3") (pintype "power_in"))
      (node (ref "R10") (pin "2") (pinfunction "2_2") (pintype "passive"))
      (node (ref "R11") (pin "2") (pinfunction "2_2") (pintype "passive"))
      (node (ref "R12") (pin "2") (pinfunction "2_2") (pintype "passive"))
      (node (ref "R13") (pin "2") (pinfunction "2_2") (pintype "passive"))
      (node (ref "R6") (pin "1") (pinfunction "1_1") (pintype "passive"))
    )
    (net (code "12") (name "Net-(*2-Pad3)") (class "Default")
      (node (ref "*2") (pin "3") (pinfunction "3_3") (pintype "power_in"))
      (node (ref "R20") (pin "1") (pinfunction "1_1") (pintype "passive"))
      (node (ref "R23") (pin "2") (pinfunction "2_2") (pintype "passive"))
      (node (ref "R24") (pin "2") (pinfunction "2_2") (pintype "passive"))
      (node (ref "R25") (pin "2") (pinfunction "2_2") (pintype "passive"))
      (node (ref "R26") (pin "2") (pinfunction "2_2") (pintype "passive"))
    )
    (net (code "13") (name "Net-(B1-ADJUSTMENT)") (class "Default")
      (node (ref "B1") (pin "1") (pinfunction "ADJUSTMENT_1") (pintype "passive"))
      (node (ref "C2") (pin "N") (pinfunction "N_N") (pintype "passive"))
      (node (ref "D2") (pin "C") (pinfunction "K_C") (pintype "passive"))
      (node (ref "R3") (pin "1") (pinfunction "1_1") (pintype "passive"))
      (node (ref "R8") (pin "2") (pinfunction "2_2") (pintype "passive"))
    )
    (net (code "14") (name "Net-(C6-Pad2)") (class "Default")
      (node (ref "C6") (pin "2") (pinfunction "2_2") (pintype "passive"))
      (node (ref "R7") (pin "1") (pinfunction "1_1") (pintype "passive"))
    )
    (net (code "15") (name "Net-(C7-Pad2)") (class "Default")
      (node (ref "C7") (pin "2") (pinfunction "2_2") (pintype "passive"))
      (node (ref "D3") (pin "A") (pinfunction "A_A") (pintype "passive"))
      (node (ref "R9") (pin "1") (pinfunction "1_1") (pintype "passive"))
    )
    (net (code "16") (name "Net-(C11-Pad2)") (class "Default")
      (node (ref "C11") (pin "2") (pinfunction "2_2") (pintype "passive"))
      (node (ref "R21") (pin "1") (pinfunction "1_1") (pintype "passive"))
    )
    (net (code "17") (name "Net-(C12-Pad2)") (class "Default")
      (node (ref "C12") (pin "2") (pinfunction "2_2") (pintype "passive"))
      (node (ref "D10") (pin "A") (pinfunction "A_A") (pintype "passive"))
      (node (ref "R22") (pin "1") (pinfunction "1_1") (pintype "passive"))
    )
    (net (code "18") (name "Net-(D1-K)") (class "Default")
      (node (ref "D1") (pin "1") (pinfunction "K_1") (pintype "passive"))
      (node (ref "Q1") (pin "1") (pinfunction "B_1") (pintype "passive"))
      (node (ref "R1") (pin "2") (pinfunction "2_2") (pintype "passive"))
    )
    (net (code "19") (name "Net-(D7-K)") (class "Default")
      (node (ref "D7") (pin "1") (pinfunction "K_1") (pintype "passive"))
      (node (ref "Q3") (pin "1") (pinfunction "B_1") (pintype "passive"))
      (node (ref "R16") (pin "2") (pinfunction "2_2") (pintype "passive"))
    )
    (net (code "20") (name "Net-(Q1-E)") (class "Default")
      (node (ref "Q1") (pin "3") (pinfunction "E_3") (pintype "passive"))
      (node (ref "Q2") (pin "1") (pinfunction "B_1") (pintype "passive"))
      (node (ref "R2") (pin "2") (pinfunction "2_2") (pintype "passive"))
    )
    (net (code "21") (name "Net-(Q2-E)") (class "Default")
      (node (ref "Q2") (pin "3") (pinfunction "E_3") (pintype "passive"))
      (node (ref "R2") (pin "1") (pinfunction "1_1") (pintype "passive"))
      (node (ref "R4") (pin "1") (pinfunction "1_1") (pintype "passive"))
    )
    (net (code "22") (name "Net-(Q3-E)") (class "Default")
      (node (ref "Q3") (pin "3") (pinfunction "E_3") (pintype "passive"))
      (node (ref "Q4") (pin "1") (pinfunction "B_1") (pintype "passive"))
      (node (ref "R17") (pin "2") (pinfunction "2_2") (pintype "passive"))
    )
    (net (code "23") (name "Net-(Q4-E)") (class "Default")
      (node (ref "Q4") (pin "3") (pinfunction "E_3") (pintype "passive"))
      (node (ref "R17") (pin "1") (pinfunction "1_1") (pintype "passive"))
      (node (ref "R18") (pin "1") (pinfunction "1_1") (pintype "passive"))
    )
    (net (code "24") (name "Net-(R3-Pad2)") (class "Default")
      (node (ref "R3") (pin "2") (pinfunction "2_2") (pintype "passive"))
      (node (ref "RV1") (pin "1") (pinfunction "1_1") (pintype "passive"))
    )
    (net (code "25") (name "Net-(R10-Pad1)") (class "Default")
      (node (ref "R10") (pin "1") (pinfunction "1_1") (pintype "passive"))
      (node (ref "R11") (pin "1") (pinfunction "1_1") (pintype "passive"))
      (node (ref "R14") (pin "2") (pinfunction "2_2") (pintype "passive"))
      (node (ref "R15") (pin "2") (pinfunction "2_2") (pintype "passive"))
    )
    (net (code "26") (name "Net-(R23-Pad1)") (class "Default")
      (node (ref "R23") (pin "1") (pinfunction "1_1") (pintype "passive"))
      (node (ref "R24") (pin "1") (pinfunction "1_1") (pintype "passive"))
      (node (ref "R27") (pin "2") (pinfunction "2_2") (pintype "passive"))
      (node (ref "R28") (pin "2") (pinfunction "2_2") (pintype "passive"))
    )
    (net (code "27") (name "Net-(VR1-ADJ{slash}GND)") (class "Default")
      (node (ref "*1") (pin "2") (pinfunction "2_2") (pintype "power_in"))
      (node (ref "R5") (pin "2") (pinfunction "2_2") (pintype "passive"))
      (node (ref "R9") (pin "2") (pinfunction "2_2") (pintype "passive"))
      (node (ref "VR1") (pin "1") (pinfunction "ADJ/GND_1") (pintype "power_in"))
    )
    (net (code "28") (name "Net-(VR1-INPUT)") (class "Default")
      (node (ref "R4") (pin "2") (pinfunction "2_2") (pintype "passive"))
      (node (ref "VR1") (pin "3") (pinfunction "INPUT_3") (pintype "input"))
    )
    (net (code "29") (name "Net-(VR2-ADJ{slash}GND)") (class "Default")
      (node (ref "*2") (pin "2") (pinfunction "2_2") (pintype "power_in"))
      (node (ref "R19") (pin "2") (pinfunction "2_2") (pintype "passive"))
      (node (ref "R22") (pin "2") (pinfunction "2_2") (pintype "passive"))
      (node (ref "VR2") (pin "1") (pinfunction "ADJ/GND_1") (pintype "power_in"))
    )
    (net (code "30") (name "Net-(VR2-INPUT)") (class "Default")
      (node (ref "R18") (pin "2") (pinfunction "2_2") (pintype "passive"))
      (node (ref "VR2") (pin "3") (pinfunction "INPUT_3") (pintype "input"))
    )
  )
)
